# Power-MCU.net
KiCad netlist of a schematic drawn in Altium Designer
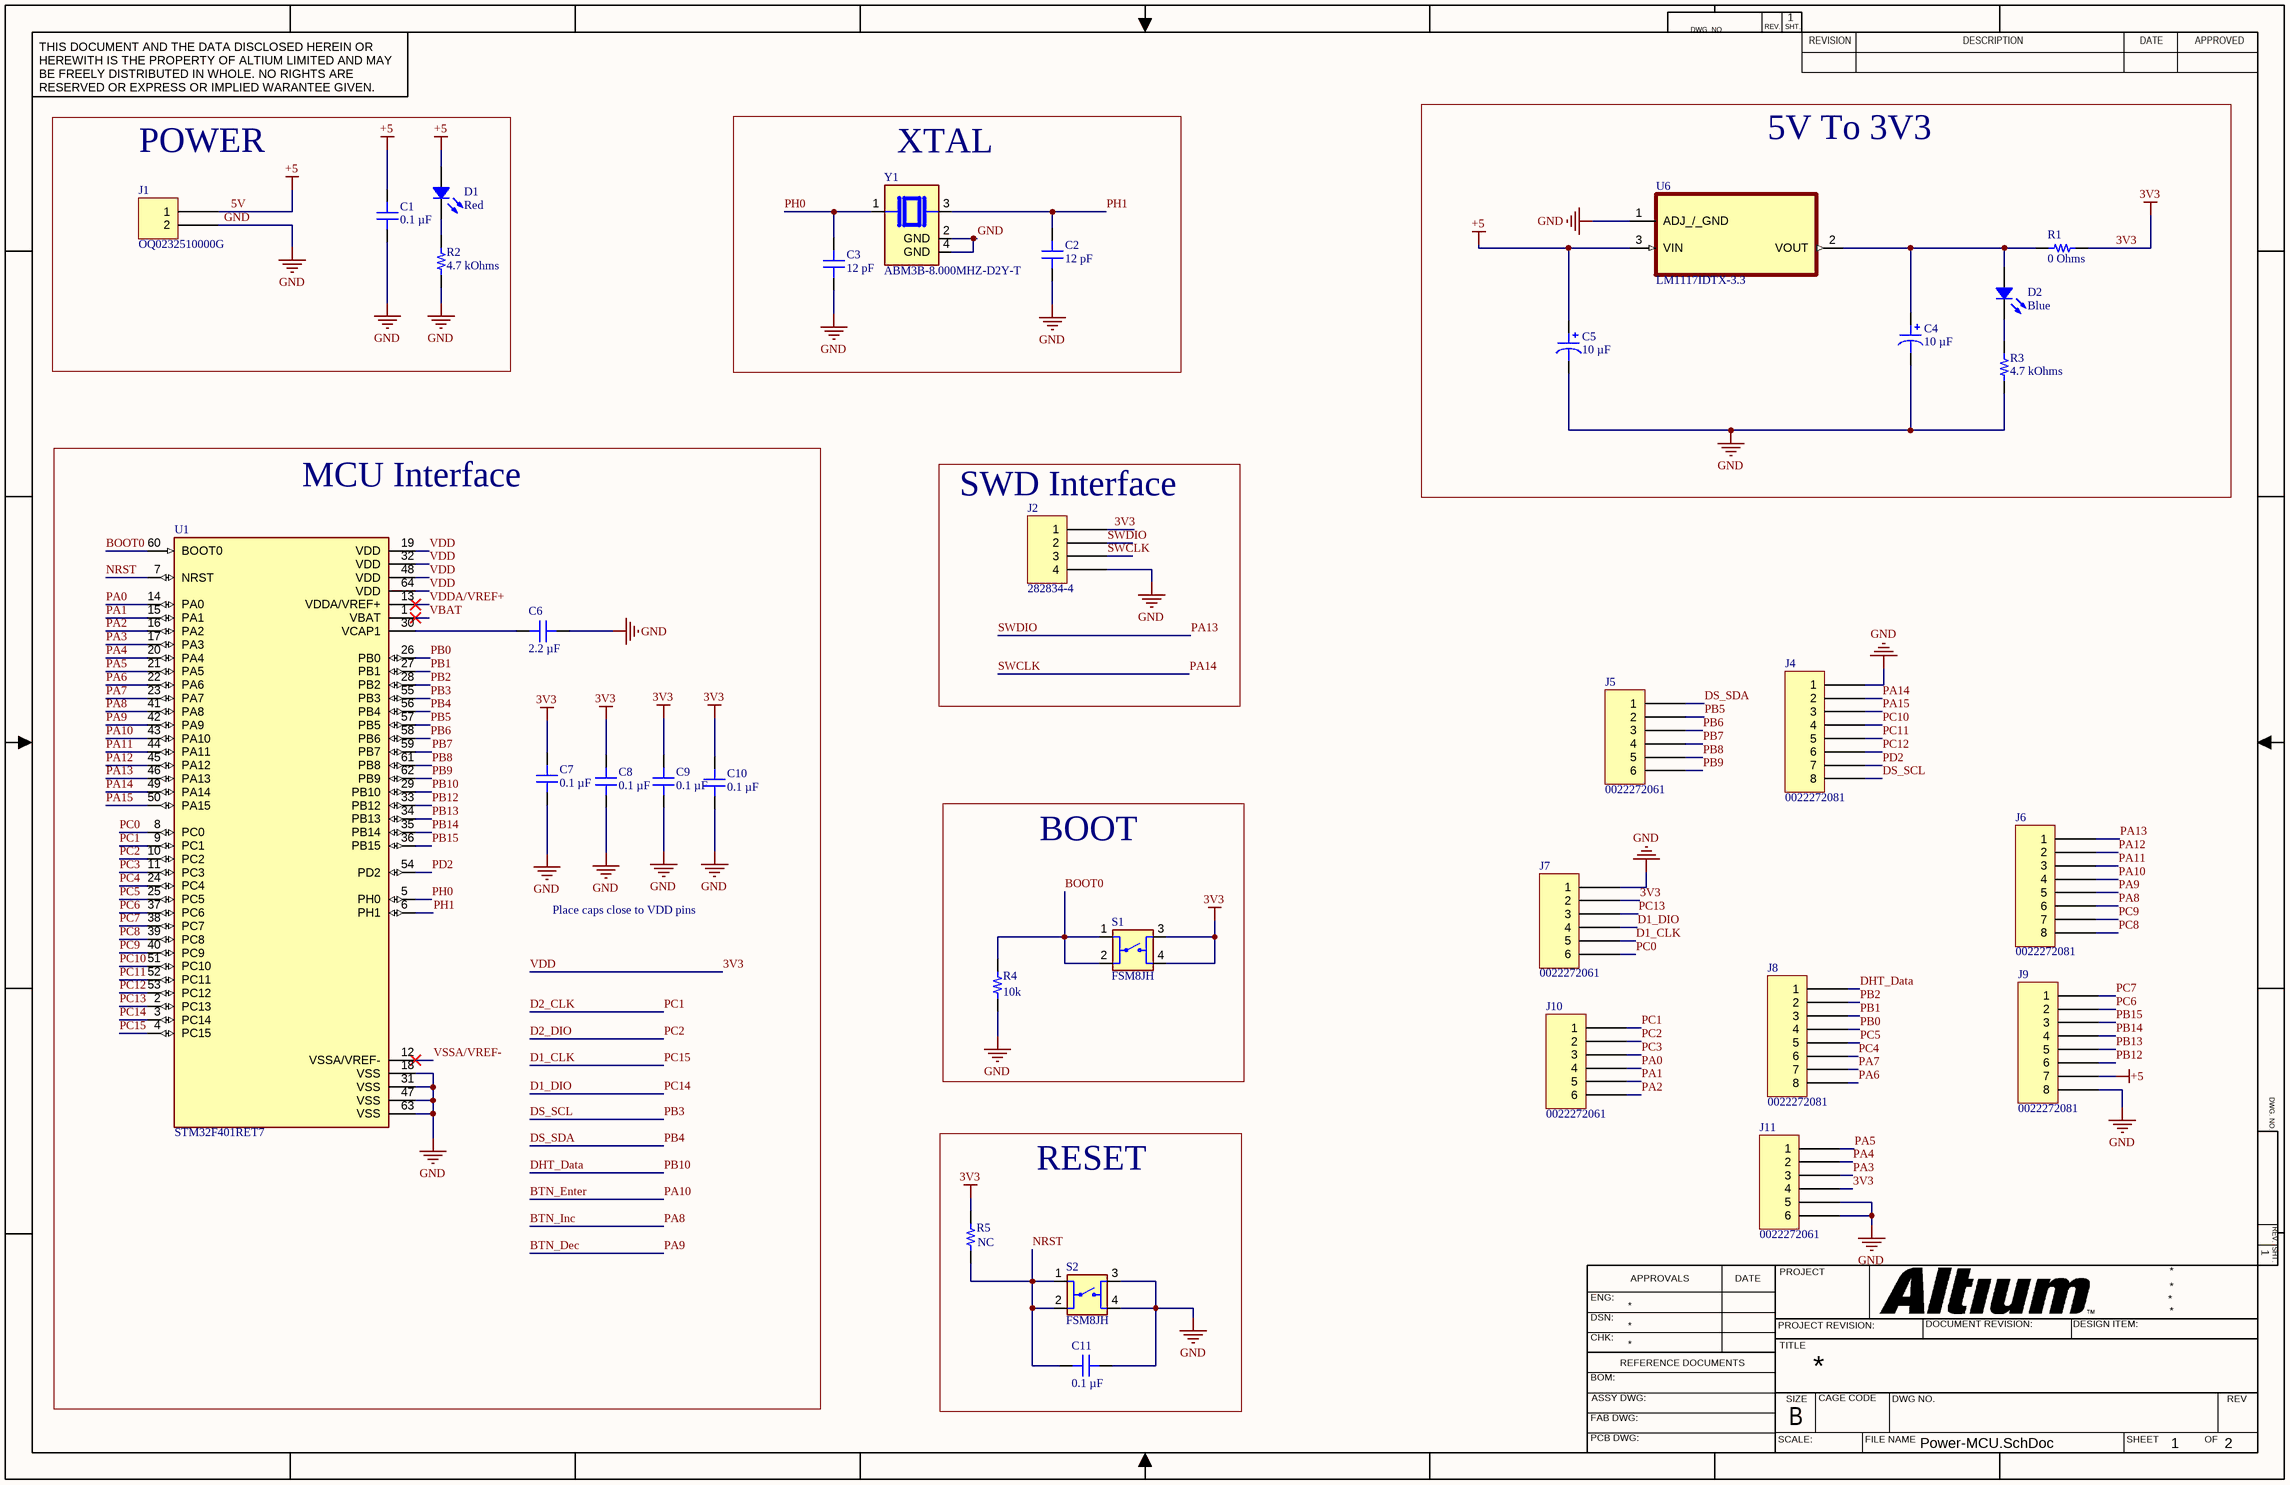
[diagram p0: Power-MCU.SchDoc]

(export (version "E")
  (design (tool "Eeschema 10.0.6"))
  (components
    (comp (ref "C1")
      (value "0.1 µF")
      (footprint "CAP 0805_2012")
      (description "CAP CER 0.1UF 100V X5R 0805")
      (fields
        (field (name "PART NUMBER") "HMK212BJ104KG-T")
        (field (name "CAPACITANCE") "0.1 µF")
        (field (name "MANUFACTURER") "Taiyo Yuden")
      )
      (libsource (lib "Celestial Altium Library - altium_library") (part "Capacitor"))
    )
    (comp (ref "C2")
      (value "12 pF")
      (footprint "CAP 0402_1005")
      (description "CAP CER 12PF 50V C0G/NP0 0402")
      (fields
        (field (name "PART NUMBER") "CBR04C120F5GAC")
        (field (name "CAPACITANCE") "12 pF")
        (field (name "MANUFACTURER") "KEMET")
      )
      (libsource (lib "Celestial Altium Library - altium_library") (part "Capacitor"))
    )
    (comp (ref "C3")
      (value "12 pF")
      (footprint "CAP 0402_1005")
      (description "CAP CER 12PF 50V C0G/NP0 0402")
      (fields
        (field (name "PART NUMBER") "CBR04C120F5GAC")
        (field (name "CAPACITANCE") "12 pF")
        (field (name "MANUFACTURER") "KEMET")
      )
      (libsource (lib "Celestial Altium Library - altium_library") (part "Capacitor"))
    )
    (comp (ref "C4")
      (value "10 µF")
      (footprint "CAP POL 1411_3528")
      (description "CAP TANT 10UF 10% 16V 1411")
      (fields (field (name "PART NUMBER") "T491T106K016AT") (field (name "MANUFACTURER") "KEMET"))
      (libsource (lib "Celestial Altium Library - altium_library") (part "Polarised Capacitor"))
    )
    (comp (ref "C5")
      (value "10 µF")
      (footprint "CAP POL 1411_3528")
      (description "CAP TANT 10UF 10% 16V 1411")
      (fields (field (name "PART NUMBER") "T491T106K016AT") (field (name "MANUFACTURER") "KEMET"))
      (libsource (lib "Celestial Altium Library - altium_library") (part "Polarised Capacitor"))
    )
    (comp (ref "C6")
      (value "2.2 µF")
      (footprint "CAP 0805_2012")
      (description "CAP CER 2.2UF 50V X5R 0805")
      (fields
        (field (name "PART NUMBER") "CL21A225KB9LNNC")
        (field (name "CAPACITANCE") "2.2 µF")
        (field (name "MANUFACTURER") "Samsung Electro-Mechanics")
      )
      (libsource (lib "Celestial Altium Library - altium_library") (part "Capacitor"))
    )
    (comp (ref "C7")
      (value "0.1 µF")
      (footprint "CAP 0805_2012")
      (description "CAP CER 0.1UF 100V X5R 0805")
      (fields
        (field (name "PART NUMBER") "HMK212BJ104KG-T")
        (field (name "CAPACITANCE") "0.1 µF")
        (field (name "MANUFACTURER") "Taiyo Yuden")
      )
      (libsource (lib "Celestial Altium Library - altium_library") (part "Capacitor"))
    )
    (comp (ref "C8")
      (value "0.1 µF")
      (footprint "CAP 0805_2012")
      (description "CAP CER 0.1UF 100V X5R 0805")
      (fields
        (field (name "PART NUMBER") "HMK212BJ104KG-T")
        (field (name "CAPACITANCE") "0.1 µF")
        (field (name "MANUFACTURER") "Taiyo Yuden")
      )
      (libsource (lib "Celestial Altium Library - altium_library") (part "Capacitor"))
    )
    (comp (ref "C9")
      (value "0.1 µF")
      (footprint "CAP 0805_2012")
      (description "CAP CER 0.1UF 100V X5R 0805")
      (fields
        (field (name "PART NUMBER") "HMK212BJ104KG-T")
        (field (name "CAPACITANCE") "0.1 µF")
        (field (name "MANUFACTURER") "Taiyo Yuden")
      )
      (libsource (lib "Celestial Altium Library - altium_library") (part "Capacitor"))
    )
    (comp (ref "C10")
      (value "0.1 µF")
      (footprint "CAP 0805_2012")
      (description "CAP CER 0.1UF 100V X5R 0805")
      (fields
        (field (name "PART NUMBER") "HMK212BJ104KG-T")
        (field (name "CAPACITANCE") "0.1 µF")
        (field (name "MANUFACTURER") "Taiyo Yuden")
      )
      (libsource (lib "Celestial Altium Library - altium_library") (part "Capacitor"))
    )
    (comp (ref "C11")
      (value "0.1 µF")
      (footprint "CAP 0805_2012")
      (description "CAP CER 0.1UF 100V X5R 0805")
      (fields
        (field (name "PART NUMBER") "HMK212BJ104KG-T")
        (field (name "CAPACITANCE") "0.1 µF")
        (field (name "MANUFACTURER") "Taiyo Yuden")
      )
      (libsource (lib "Celestial Altium Library - altium_library") (part "Capacitor"))
    )
    (comp (ref "D1")
      (value "Red")
      (footprint "LED 0805_2012 RED")
      (description "LED RED CLEAR 0805 SMD")
      (fields (field (name "PART NUMBER") "SM0805URC") (field (name "MANUFACTURER") "Bivar Inc."))
      (libsource (lib "Celestial Altium Library - altium_library") (part "LED"))
    )
    (comp (ref "D2")
      (value "Blue")
      (footprint "LED 0805_2012 RED")
      (description "LED RED CLEAR 0805 SMD")
      (fields (field (name "PART NUMBER") "SM0805URC") (field (name "MANUFACTURER") "Bivar Inc."))
      (libsource (lib "Celestial Altium Library - altium_library") (part "LED"))
    )
    (comp (ref "J1")
      (value "OQ0232510000G")
      (footprint "FCI 06-381-2PIN")
      (description "TERM BLOCK HDR 2POS 90DEG 3.81MM")
      (fields (field (name "MANUFACTURER") "Amphenol Anytek"))
      (libsource (lib "Celestial Altium Library - altium_library") (part "2 Pin"))
    )
    (comp (ref "J2")
      (value "282834-4")
      (footprint "TE 282834-4")
      (description "TERM BLK 4P SIDE ENT 2.54MM PCB")
      (fields (field (name "MANUFACTURER") "TE Connectivity AMP Connectors") (field (name "VOLTAGE") "150V"))
      (libsource (lib "Celestial Altium Library - altium_library") (part "4 Pin"))
    )
    (comp (ref "J4")
      (value "0022272081")
      (footprint "MOLEX KK 0022272081")
      (description "CONN HEADER VERT 8POS 2.54MM")
      (fields (field (name "MANUFACTURER") "Molex"))
      (libsource (lib "Celestial Altium Library - altium_library") (part "8 Pin"))
    )
    (comp (ref "J5")
      (value "0022272061")
      (footprint "MOLEX KK 0022272061")
      (description "CONN HEADER VERT 6POS 2.54MM")
      (fields (field (name "MANUFACTURER") "Molex"))
      (libsource (lib "Celestial Altium Library - altium_library") (part "6 Pin"))
    )
    (comp (ref "J6")
      (value "0022272081")
      (footprint "MOLEX KK 0022272081")
      (description "CONN HEADER VERT 8POS 2.54MM")
      (fields (field (name "MANUFACTURER") "Molex"))
      (libsource (lib "Celestial Altium Library - altium_library") (part "8 Pin"))
    )
    (comp (ref "J7")
      (value "0022272061")
      (footprint "MOLEX KK 0022272061")
      (description "CONN HEADER VERT 6POS 2.54MM")
      (fields (field (name "MANUFACTURER") "Molex"))
      (libsource (lib "Celestial Altium Library - altium_library") (part "6 Pin"))
    )
    (comp (ref "J8")
      (value "0022272081")
      (footprint "MOLEX KK 0022272081")
      (description "CONN HEADER VERT 8POS 2.54MM")
      (fields (field (name "MANUFACTURER") "Molex"))
      (libsource (lib "Celestial Altium Library - altium_library") (part "8 Pin"))
    )
    (comp (ref "J9")
      (value "0022272081")
      (footprint "MOLEX KK 0022272081")
      (description "CONN HEADER VERT 8POS 2.54MM")
      (fields (field (name "MANUFACTURER") "Molex"))
      (libsource (lib "Celestial Altium Library - altium_library") (part "8 Pin"))
    )
    (comp (ref "J10")
      (value "0022272061")
      (footprint "MOLEX KK 0022272061")
      (description "CONN HEADER VERT 6POS 2.54MM")
      (fields (field (name "MANUFACTURER") "Molex"))
      (libsource (lib "Celestial Altium Library - altium_library") (part "6 Pin"))
    )
    (comp (ref "J11")
      (value "0022272061")
      (footprint "MOLEX KK 0022272061")
      (description "CONN HEADER VERT 6POS 2.54MM")
      (fields (field (name "MANUFACTURER") "Molex"))
      (libsource (lib "Celestial Altium Library - altium_library") (part "6 Pin"))
    )
    (comp (ref "R1")
      (value "0 Ohms")
      (footprint "RES 0805_2012")
      (description "RES 0 OHM JUMPER 0805")
      (fields
        (field (name "PART NUMBER") "TLRZ2ATTD")
        (field (name "MANUFACTURER") "KOA Speer Electronics, Inc.")
      )
      (libsource (lib "Celestial Altium Library - altium_library") (part "Resistor"))
    )
    (comp (ref "R2")
      (value "4.7 kOhms")
      (footprint "RES 0805_2012")
      (description "CRGH0805 1% 4K7 0.33W")
      (fields
        (field (name "PART NUMBER") "CRGH0805F4K7")
        (field (name "MANUFACTURER") "TE Connectivity Passive Product")
      )
      (libsource (lib "Celestial Altium Library - altium_library") (part "Resistor"))
    )
    (comp (ref "R3")
      (value "4.7 kOhms")
      (footprint "RES 0805_2012")
      (description "CRGH0805 1% 4K7 0.33W")
      (fields
        (field (name "PART NUMBER") "CRGH0805F4K7")
        (field (name "MANUFACTURER") "TE Connectivity Passive Product")
      )
      (libsource (lib "Celestial Altium Library - altium_library") (part "Resistor"))
    )
    (comp (ref "R4")
      (value "10k Ohms")
      (footprint "RES 0805_2012")
      (description "RES 0 OHM JUMPER 0805")
      (fields
        (field (name "PART NUMBER") "TLRZ2ATTD")
        (field (name "MANUFACTURER") "KOA Speer Electronics, Inc.")
      )
      (libsource (lib "Celestial Altium Library - altium_library") (part "Resistor"))
    )
    (comp (ref "R5")
      (value "NC")
      (footprint "RES 0805_2012")
      (description "RES 0 OHM JUMPER 0805")
      (fields
        (field (name "PART NUMBER") "TLRZ2ATTD")
        (field (name "MANUFACTURER") "KOA Speer Electronics, Inc.")
      )
      (libsource (lib "Celestial Altium Library - altium_library") (part "Resistor"))
    )
    (comp (ref "S1")
      (value "FSM8JH")
      (footprint "SW_FSM8JH")
      (description "Tactile Switch SPST-NO Top Actuated Through Hole")
      (fields (field (name "MF") "TE Connectivity"))
      (libsource (lib "MyAltLib") (part "FSM8JH"))
    )
    (comp (ref "S2")
      (value "FSM8JH")
      (footprint "SW_FSM8JH")
      (description "Tactile Switch SPST-NO Top Actuated Through Hole")
      (fields (field (name "MF") "TE Connectivity"))
      (libsource (lib "MyAltLib") (part "FSM8JH"))
    )
    (comp (ref "U1")
      (value "STM32F401RET7")
      (footprint "LQFP-64")
      (description "ARMÂ®CortexÂ®-M4STM32F4å¾®æŽ§åˆ¶å™¨IC 32ä½84MHz 512KBï¼ˆ512K x 8ï¼‰FLASH 64-LQFPï¼ˆ10x10ï¼‰")
      (fields (field (name "MF") "STMicroelectronics"))
      (libsource (lib "MyAltLib") (part "STM32F401RET7"))
    )
    (comp (ref "U6")
      (value "LM1117IDTX-3.3")
      (footprint "TO252-3")
      (description "Linear Voltage Regulator IC 1 Output 800mA TO-252-3")
      (fields
        (field (name "MF") "Texas Instruments")
        (field (name "DIGI-KEY_PART_NUMBER") "LM1117IDTX-3.3/NOPBCT-ND")
      )
      (libsource (lib "MyAltLib") (part "LM1117IDTX-3.3"))
    )
    (comp (ref "Y1")
      (value "ABM3B-8.000MHZ-D2Y-T")
      (footprint "XTAL_ABM3B-8.000MHZ-D2Y-T")
      (description "Crystal 8MHz Â±20ppm (Tol) Â±30ppm (Stability) 18pF FUND 200Ohm 4-Pin CSMD T/R")
      (fields (field (name "MF") "Abracon LLC"))
      (libsource (lib "MyAltLib") (part "ABM3B-8.000MHZ-D2Y-T"))
    )
  )
  (nets
    (net (code "1") (name "+5") (class "Default")
      (node (ref "C1") (pin "2") (pinfunction "2_2") (pintype "passive"))
      (node (ref "C5") (pin "1") (pinfunction "1_1") (pintype "passive"))
      (node (ref "D1") (pin "1") (pinfunction "1_1") (pintype "passive"))
      (node (ref "J1") (pin "1") (pinfunction "1_1") (pintype "passive"))
      (node (ref "J9") (pin "7") (pinfunction "7_7") (pintype "passive"))
      (node (ref "U6") (pin "3") (pinfunction "VIN_3") (pintype "input"))
    )
    (net (code "2") (name "/BOOT0") (class "Default")
      (node (ref "R4") (pin "2") (pinfunction "2_2") (pintype "passive"))
      (node (ref "S1") (pin "1") (pinfunction "1_1") (pintype "passive"))
      (node (ref "S1") (pin "2") (pinfunction "2_2") (pintype "passive"))
      (node (ref "U1") (pin "60") (pinfunction "BOOT0_60") (pintype "input"))
    )
    (net (code "3") (name "/BTN_Dec") (class "Default")
      (node (ref "J6") (pin "5") (pinfunction "5_5") (pintype "passive"))
      (node (ref "U1") (pin "42") (pinfunction "PA9_42") (pintype "bidirectional"))
    )
    (net (code "4") (name "/BTN_Enter") (class "Default")
      (node (ref "J6") (pin "4") (pinfunction "4_4") (pintype "passive"))
      (node (ref "U1") (pin "43") (pinfunction "PA10_43") (pintype "bidirectional"))
    )
    (net (code "5") (name "/BTN_Inc") (class "Default")
      (node (ref "J6") (pin "6") (pinfunction "6_6") (pintype "passive"))
      (node (ref "U1") (pin "41") (pinfunction "PA8_41") (pintype "bidirectional"))
    )
    (net (code "6") (name "/D1_CLK") (class "Default")
      (node (ref "J7") (pin "5") (pinfunction "5_5") (pintype "passive"))
      (node (ref "U1") (pin "4") (pinfunction "PC15_4") (pintype "bidirectional"))
    )
    (net (code "7") (name "/D1_DIO") (class "Default")
      (node (ref "J7") (pin "4") (pinfunction "4_4") (pintype "passive"))
      (node (ref "U1") (pin "3") (pinfunction "PC14_3") (pintype "bidirectional"))
    )
    (net (code "8") (name "/D2_CLK") (class "Default")
      (node (ref "J10") (pin "1") (pinfunction "1_1") (pintype "passive"))
      (node (ref "U1") (pin "9") (pinfunction "PC1_9") (pintype "bidirectional"))
    )
    (net (code "9") (name "/D2_DIO") (class "Default")
      (node (ref "J10") (pin "2") (pinfunction "2_2") (pintype "passive"))
      (node (ref "U1") (pin "10") (pinfunction "PC2_10") (pintype "bidirectional"))
    )
    (net (code "10") (name "/DHT_Data") (class "Default")
      (node (ref "J8") (pin "1") (pinfunction "1_1") (pintype "passive"))
      (node (ref "U1") (pin "29") (pinfunction "PB10_29") (pintype "bidirectional"))
    )
    (net (code "11") (name "/DS_SCL") (class "Default")
      (node (ref "J4") (pin "8") (pinfunction "8_8") (pintype "passive"))
      (node (ref "U1") (pin "55") (pinfunction "PB3_55") (pintype "bidirectional"))
    )
    (net (code "12") (name "/DS_SDA") (class "Default")
      (node (ref "J5") (pin "1") (pinfunction "1_1") (pintype "passive"))
      (node (ref "U1") (pin "56") (pinfunction "PB4_56") (pintype "bidirectional"))
    )
    (net (code "13") (name "/NRST") (class "Default")
      (node (ref "C11") (pin "2") (pinfunction "2_2") (pintype "passive"))
      (node (ref "R5") (pin "1") (pinfunction "1_1") (pintype "passive"))
      (node (ref "S2") (pin "1") (pinfunction "1_1") (pintype "passive"))
      (node (ref "S2") (pin "2") (pinfunction "2_2") (pintype "passive"))
      (node (ref "U1") (pin "7") (pinfunction "NRST_7") (pintype "bidirectional"))
    )
    (net (code "14") (name "/PA0") (class "Default")
      (node (ref "J10") (pin "4") (pinfunction "4_4") (pintype "passive"))
      (node (ref "U1") (pin "14") (pinfunction "PA0_14") (pintype "bidirectional"))
    )
    (net (code "15") (name "/PA1") (class "Default")
      (node (ref "J10") (pin "5") (pinfunction "5_5") (pintype "passive"))
      (node (ref "U1") (pin "15") (pinfunction "PA1_15") (pintype "bidirectional"))
    )
    (net (code "16") (name "/PA2") (class "Default")
      (node (ref "J10") (pin "6") (pinfunction "6_6") (pintype "passive"))
      (node (ref "U1") (pin "16") (pinfunction "PA2_16") (pintype "bidirectional"))
    )
    (net (code "17") (name "/PA3") (class "Default")
      (node (ref "J11") (pin "3") (pinfunction "3_3") (pintype "passive"))
      (node (ref "U1") (pin "17") (pinfunction "PA3_17") (pintype "bidirectional"))
    )
    (net (code "18") (name "/PA4") (class "Default")
      (node (ref "J11") (pin "2") (pinfunction "2_2") (pintype "passive"))
      (node (ref "U1") (pin "20") (pinfunction "PA4_20") (pintype "bidirectional"))
    )
    (net (code "19") (name "/PA5") (class "Default")
      (node (ref "J11") (pin "1") (pinfunction "1_1") (pintype "passive"))
      (node (ref "U1") (pin "21") (pinfunction "PA5_21") (pintype "bidirectional"))
    )
    (net (code "20") (name "/PA6") (class "Default")
      (node (ref "J8") (pin "8") (pinfunction "8_8") (pintype "passive"))
      (node (ref "U1") (pin "22") (pinfunction "PA6_22") (pintype "bidirectional"))
    )
    (net (code "21") (name "/PA7") (class "Default")
      (node (ref "J8") (pin "7") (pinfunction "7_7") (pintype "passive"))
      (node (ref "U1") (pin "23") (pinfunction "PA7_23") (pintype "bidirectional"))
    )
    (net (code "22") (name "/PA11") (class "Default")
      (node (ref "J6") (pin "3") (pinfunction "3_3") (pintype "passive"))
      (node (ref "U1") (pin "44") (pinfunction "PA11_44") (pintype "bidirectional"))
    )
    (net (code "23") (name "/PA12") (class "Default")
      (node (ref "J6") (pin "2") (pinfunction "2_2") (pintype "passive"))
      (node (ref "U1") (pin "45") (pinfunction "PA12_45") (pintype "bidirectional"))
    )
    (net (code "24") (name "/PA13") (class "Default")
      (node (ref "J2") (pin "2") (pinfunction "2_2") (pintype "passive"))
      (node (ref "J6") (pin "1") (pinfunction "1_1") (pintype "passive"))
      (node (ref "U1") (pin "46") (pinfunction "PA13_46") (pintype "bidirectional"))
    )
    (net (code "25") (name "/PA14") (class "Default")
      (node (ref "J2") (pin "3") (pinfunction "3_3") (pintype "passive"))
      (node (ref "J4") (pin "2") (pinfunction "2_2") (pintype "passive"))
      (node (ref "U1") (pin "49") (pinfunction "PA14_49") (pintype "bidirectional"))
    )
    (net (code "26") (name "/PA15") (class "Default")
      (node (ref "J4") (pin "3") (pinfunction "3_3") (pintype "passive"))
      (node (ref "U1") (pin "50") (pinfunction "PA15_50") (pintype "bidirectional"))
    )
    (net (code "27") (name "/PB0") (class "Default")
      (node (ref "J8") (pin "4") (pinfunction "4_4") (pintype "passive"))
      (node (ref "U1") (pin "26") (pinfunction "PB0_26") (pintype "bidirectional"))
    )
    (net (code "28") (name "/PB1") (class "Default")
      (node (ref "J8") (pin "3") (pinfunction "3_3") (pintype "passive"))
      (node (ref "U1") (pin "27") (pinfunction "PB1_27") (pintype "bidirectional"))
    )
    (net (code "29") (name "/PB2") (class "Default")
      (node (ref "J8") (pin "2") (pinfunction "2_2") (pintype "passive"))
      (node (ref "U1") (pin "28") (pinfunction "PB2_28") (pintype "bidirectional"))
    )
    (net (code "30") (name "/PB5") (class "Default")
      (node (ref "J5") (pin "2") (pinfunction "2_2") (pintype "passive"))
      (node (ref "U1") (pin "57") (pinfunction "PB5_57") (pintype "bidirectional"))
    )
    (net (code "31") (name "/PB6") (class "Default")
      (node (ref "J5") (pin "3") (pinfunction "3_3") (pintype "passive"))
      (node (ref "U1") (pin "58") (pinfunction "PB6_58") (pintype "bidirectional"))
    )
    (net (code "32") (name "/PB7") (class "Default")
      (node (ref "J5") (pin "4") (pinfunction "4_4") (pintype "passive"))
      (node (ref "U1") (pin "59") (pinfunction "PB7_59") (pintype "bidirectional"))
    )
    (net (code "33") (name "/PB8") (class "Default")
      (node (ref "J5") (pin "5") (pinfunction "5_5") (pintype "passive"))
      (node (ref "U1") (pin "61") (pinfunction "PB8_61") (pintype "bidirectional"))
    )
    (net (code "34") (name "/PB9") (class "Default")
      (node (ref "J5") (pin "6") (pinfunction "6_6") (pintype "passive"))
      (node (ref "U1") (pin "62") (pinfunction "PB9_62") (pintype "bidirectional"))
    )
    (net (code "35") (name "/PB12") (class "Default")
      (node (ref "J9") (pin "6") (pinfunction "6_6") (pintype "passive"))
      (node (ref "U1") (pin "33") (pinfunction "PB12_33") (pintype "bidirectional"))
    )
    (net (code "36") (name "/PB13") (class "Default")
      (node (ref "J9") (pin "5") (pinfunction "5_5") (pintype "passive"))
      (node (ref "U1") (pin "34") (pinfunction "PB13_34") (pintype "bidirectional"))
    )
    (net (code "37") (name "/PB14") (class "Default")
      (node (ref "J9") (pin "4") (pinfunction "4_4") (pintype "passive"))
      (node (ref "U1") (pin "35") (pinfunction "PB14_35") (pintype "bidirectional"))
    )
    (net (code "38") (name "/PB15") (class "Default")
      (node (ref "J9") (pin "3") (pinfunction "3_3") (pintype "passive"))
      (node (ref "U1") (pin "36") (pinfunction "PB15_36") (pintype "bidirectional"))
    )
    (net (code "39") (name "/PC0") (class "Default")
      (node (ref "J7") (pin "6") (pinfunction "6_6") (pintype "passive"))
      (node (ref "U1") (pin "8") (pinfunction "PC0_8") (pintype "bidirectional"))
    )
    (net (code "40") (name "/PC3") (class "Default")
      (node (ref "J10") (pin "3") (pinfunction "3_3") (pintype "passive"))
      (node (ref "U1") (pin "11") (pinfunction "PC3_11") (pintype "bidirectional"))
    )
    (net (code "41") (name "/PC4") (class "Default")
      (node (ref "J8") (pin "6") (pinfunction "6_6") (pintype "passive"))
      (node (ref "U1") (pin "24") (pinfunction "PC4_24") (pintype "bidirectional"))
    )
    (net (code "42") (name "/PC5") (class "Default")
      (node (ref "J8") (pin "5") (pinfunction "5_5") (pintype "passive"))
      (node (ref "U1") (pin "25") (pinfunction "PC5_25") (pintype "bidirectional"))
    )
    (net (code "43") (name "/PC6") (class "Default")
      (node (ref "J9") (pin "2") (pinfunction "2_2") (pintype "passive"))
      (node (ref "U1") (pin "37") (pinfunction "PC6_37") (pintype "bidirectional"))
    )
    (net (code "44") (name "/PC7") (class "Default")
      (node (ref "J9") (pin "1") (pinfunction "1_1") (pintype "passive"))
      (node (ref "U1") (pin "38") (pinfunction "PC7_38") (pintype "bidirectional"))
    )
    (net (code "45") (name "/PC8") (class "Default")
      (node (ref "J6") (pin "8") (pinfunction "8_8") (pintype "passive"))
      (node (ref "U1") (pin "39") (pinfunction "PC8_39") (pintype "bidirectional"))
    )
    (net (code "46") (name "/PC9") (class "Default")
      (node (ref "J6") (pin "7") (pinfunction "7_7") (pintype "passive"))
      (node (ref "U1") (pin "40") (pinfunction "PC9_40") (pintype "bidirectional"))
    )
    (net (code "47") (name "/PC10") (class "Default")
      (node (ref "J4") (pin "4") (pinfunction "4_4") (pintype "passive"))
      (node (ref "U1") (pin "51") (pinfunction "PC10_51") (pintype "bidirectional"))
    )
    (net (code "48") (name "/PC11") (class "Default")
      (node (ref "J4") (pin "5") (pinfunction "5_5") (pintype "passive"))
      (node (ref "U1") (pin "52") (pinfunction "PC11_52") (pintype "bidirectional"))
    )
    (net (code "49") (name "/PC12") (class "Default")
      (node (ref "J4") (pin "6") (pinfunction "6_6") (pintype "passive"))
      (node (ref "U1") (pin "53") (pinfunction "PC12_53") (pintype "bidirectional"))
    )
    (net (code "50") (name "/PC13") (class "Default")
      (node (ref "J7") (pin "3") (pinfunction "3_3") (pintype "passive"))
      (node (ref "U1") (pin "2") (pinfunction "PC13_2") (pintype "bidirectional"))
    )
    (net (code "51") (name "/PD2") (class "Default")
      (node (ref "J4") (pin "7") (pinfunction "7_7") (pintype "passive"))
      (node (ref "U1") (pin "54") (pinfunction "PD2_54") (pintype "bidirectional"))
    )
    (net (code "52") (name "/PH0") (class "Default")
      (node (ref "C3") (pin "2") (pinfunction "2_2") (pintype "passive"))
      (node (ref "U1") (pin "5") (pinfunction "PH0_5") (pintype "bidirectional"))
      (node (ref "Y1") (pin "1") (pinfunction "1_1") (pintype "passive"))
    )
    (net (code "53") (name "/PH1") (class "Default")
      (node (ref "C2") (pin "2") (pinfunction "2_2") (pintype "passive"))
      (node (ref "U1") (pin "6") (pinfunction "PH1_6") (pintype "bidirectional"))
      (node (ref "Y1") (pin "3") (pinfunction "2_3") (pintype "passive"))
    )
    (net (code "54") (name "/VBAT") (class "Default")
      (node (ref "U1") (pin "1") (pinfunction "VBAT_1") (pintype "power_in+no_connect"))
    )
    (net (code "55") (name "/VDDA{slash}VREF+") (class "Default")
      (node (ref "U1") (pin "13") (pinfunction "VDDA/VREF+_13") (pintype "power_in+no_connect"))
    )
    (net (code "56") (name "/VSSA{slash}VREF-") (class "Default")
      (node (ref "U1") (pin "12") (pinfunction "VSSA/VREF-_12") (pintype "power_in+no_connect"))
    )
    (net (code "57") (name "3V3") (class "Default")
      (node (ref "C10") (pin "2") (pinfunction "2_2") (pintype "passive"))
      (node (ref "C7") (pin "2") (pinfunction "2_2") (pintype "passive"))
      (node (ref "C8") (pin "2") (pinfunction "2_2") (pintype "passive"))
      (node (ref "C9") (pin "2") (pinfunction "2_2") (pintype "passive"))
      (node (ref "J11") (pin "4") (pinfunction "4_4") (pintype "passive"))
      (node (ref "J2") (pin "1") (pinfunction "1_1") (pintype "passive"))
      (node (ref "J7") (pin "2") (pinfunction "2_2") (pintype "passive"))
      (node (ref "R1") (pin "2") (pinfunction "2_2") (pintype "passive"))
      (node (ref "R5") (pin "2") (pinfunction "2_2") (pintype "passive"))
      (node (ref "S1") (pin "3") (pinfunction "3_3") (pintype "passive"))
      (node (ref "S1") (pin "4") (pinfunction "4_4") (pintype "passive"))
      (node (ref "U1") (pin "19") (pinfunction "VDD_19") (pintype "power_in"))
      (node (ref "U1") (pin "32") (pinfunction "VDD_32") (pintype "power_in"))
      (node (ref "U1") (pin "48") (pinfunction "VDD_48") (pintype "power_in"))
      (node (ref "U1") (pin "64") (pinfunction "VDD_64") (pintype "power_in"))
    )
    (net (code "58") (name "GND") (class "Default")
      (node (ref "C1") (pin "1") (pinfunction "1_1") (pintype "passive"))
      (node (ref "C10") (pin "1") (pinfunction "1_1") (pintype "passive"))
      (node (ref "C11") (pin "1") (pinfunction "1_1") (pintype "passive"))
      (node (ref "C2") (pin "1") (pinfunction "1_1") (pintype "passive"))
      (node (ref "C3") (pin "1") (pinfunction "1_1") (pintype "passive"))
      (node (ref "C4") (pin "2") (pinfunction "2_2") (pintype "passive"))
      (node (ref "C5") (pin "2") (pinfunction "2_2") (pintype "passive"))
      (node (ref "C6") (pin "2") (pinfunction "2_2") (pintype "passive"))
      (node (ref "C7") (pin "1") (pinfunction "1_1") (pintype "passive"))
      (node (ref "C8") (pin "1") (pinfunction "1_1") (pintype "passive"))
      (node (ref "C9") (pin "1") (pinfunction "1_1") (pintype "passive"))
      (node (ref "J1") (pin "2") (pinfunction "2_2") (pintype "passive"))
      (node (ref "J11") (pin "5") (pinfunction "5_5") (pintype "passive"))
      (node (ref "J11") (pin "6") (pinfunction "6_6") (pintype "passive"))
      (node (ref "J2") (pin "4") (pinfunction "4_4") (pintype "passive"))
      (node (ref "J4") (pin "1") (pinfunction "1_1") (pintype "passive"))
      (node (ref "J7") (pin "1") (pinfunction "1_1") (pintype "passive"))
      (node (ref "J9") (pin "8") (pinfunction "8_8") (pintype "passive"))
      (node (ref "R2") (pin "1") (pinfunction "1_1") (pintype "passive"))
      (node (ref "R3") (pin "1") (pinfunction "1_1") (pintype "passive"))
      (node (ref "R4") (pin "1") (pinfunction "1_1") (pintype "passive"))
      (node (ref "S2") (pin "3") (pinfunction "3_3") (pintype "passive"))
      (node (ref "S2") (pin "4") (pinfunction "4_4") (pintype "passive"))
      (node (ref "U1") (pin "18") (pinfunction "VSS_18") (pintype "power_in"))
      (node (ref "U1") (pin "31") (pinfunction "VSS_31") (pintype "power_in"))
      (node (ref "U1") (pin "47") (pinfunction "VSS_47") (pintype "power_in"))
      (node (ref "U1") (pin "63") (pinfunction "VSS_63") (pintype "power_in"))
      (node (ref "U6") (pin "1") (pinfunction "ADJ_/_GND_1") (pintype "power_in"))
      (node (ref "Y1") (pin "2") (pinfunction "GND_2") (pintype "power_in"))
      (node (ref "Y1") (pin "4") (pinfunction "GND_4") (pintype "power_in"))
    )
    (net (code "59") (name "Net-(D1-Pad2)") (class "Default")
      (node (ref "D1") (pin "2") (pinfunction "2_2") (pintype "passive"))
      (node (ref "R2") (pin "2") (pinfunction "2_2") (pintype "passive"))
    )
    (net (code "60") (name "Net-(D2-Pad2)") (class "Default")
      (node (ref "D2") (pin "2") (pinfunction "2_2") (pintype "passive"))
      (node (ref "R3") (pin "2") (pinfunction "2_2") (pintype "passive"))
    )
    (net (code "61") (name "Net-(U1-VCAP1)") (class "Default")
      (node (ref "C6") (pin "1") (pinfunction "1_1") (pintype "passive"))
      (node (ref "U1") (pin "30") (pinfunction "VCAP1_30") (pintype "power_in"))
    )
    (net (code "62") (name "Net-(U6-VOUT)") (class "Default")
      (node (ref "C4") (pin "1") (pinfunction "1_1") (pintype "passive"))
      (node (ref "D2") (pin "1") (pinfunction "1_1") (pintype "passive"))
      (node (ref "R1") (pin "1") (pinfunction "1_1") (pintype "passive"))
      (node (ref "U6") (pin "2") (pinfunction "VOUT_2") (pintype "output"))
    )
  )
)
